# DistrValveBrd.net
KiCad netlist of a schematic drawn in Altium Designer
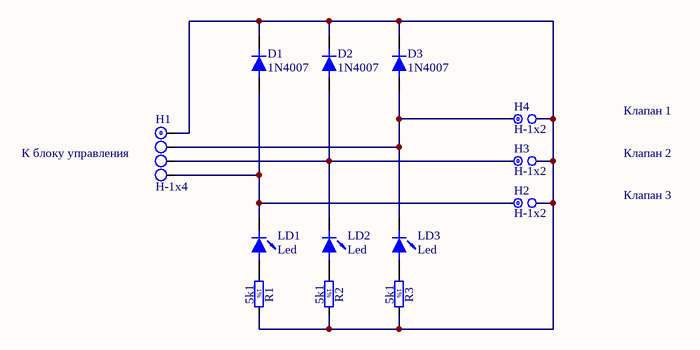
[diagram p0: DistrValveBrd.SchDoc]

(export (version "E")
  (design (tool "Eeschema 10.0.6"))
  (components
    (comp (ref "D1")
      (value "1N4007")
      (footprint "DO-41-300")
      (description "1000V 1A")
      (libsource (lib "Diodes-Power") (part "1N4007"))
    )
    (comp (ref "D2")
      (value "1N4007")
      (footprint "DO-41-300")
      (description "1000V 1A")
      (libsource (lib "Diodes-Power") (part "1N4007"))
    )
    (comp (ref "D3")
      (value "1N4007")
      (footprint "DO-41-300")
      (description "1000V 1A")
      (libsource (lib "Diodes-Power") (part "1N4007"))
    )
    (comp (ref "H1") (value "H-1x4") (footprint "J1x4") (libsource (lib "Connektor") (part "H-1x4")))
    (comp (ref "H2") (value "H-1x2") (footprint "J1x2") (libsource (lib "Connektor") (part "H-1x2")))
    (comp (ref "H3") (value "H-1x2") (footprint "J1x2") (libsource (lib "Connektor") (part "H-1x2")))
    (comp (ref "H4") (value "H-1x2") (footprint "J1x2") (libsource (lib "Connektor") (part "H-1x2")))
    (comp (ref "LD1")
      (value "Led")
      (footprint "Led d5mm")
      (description "5mm")
      (libsource (lib "Ind LED-LCD") (part "Led-5mm"))
    )
    (comp (ref "LD2")
      (value "Led")
      (footprint "Led d5mm")
      (description "5mm")
      (libsource (lib "Ind LED-LCD") (part "Led-5mm"))
    )
    (comp (ref "LD3")
      (value "Led")
      (footprint "Led d5mm")
      (description "5mm")
      (libsource (lib "Ind LED-LCD") (part "Led-5mm"))
    )
    (comp (ref "R1")
      (value "5k1")
      (footprint "RESC2012X60N")
      (description "Resistor - 1%")
      (fields
        (field (name "PART NUMBER") "R0805_5K1_1%_0.125W_100PPM")
        (field (name "POWER") "0.125W")
        (field (name "AUTHOR") "CERN DEM JLC")
      )
      (libsource (lib "Resistors") (part "Resistor - 1%"))
    )
    (comp (ref "R2")
      (value "5k1")
      (footprint "RESC2012X60N")
      (description "Resistor - 1%")
      (fields
        (field (name "PART NUMBER") "R0805_5K1_1%_0.125W_100PPM")
        (field (name "POWER") "0.125W")
        (field (name "AUTHOR") "CERN DEM JLC")
      )
      (libsource (lib "Resistors") (part "Resistor - 1%"))
    )
    (comp (ref "R3")
      (value "5k1")
      (footprint "RESC2012X60N")
      (description "Resistor - 1%")
      (fields
        (field (name "PART NUMBER") "R0805_5K1_1%_0.125W_100PPM")
        (field (name "POWER") "0.125W")
        (field (name "AUTHOR") "CERN DEM JLC")
      )
      (libsource (lib "Resistors") (part "Resistor - 1%"))
    )
  )
  (nets
    (net (code "1") (name "Net-(D1-A)") (class "Default")
      (node (ref "D1") (pin "1") (pinfunction "A_1") (pintype "passive"))
      (node (ref "H1") (pin "4") (pinfunction "4_4") (pintype "passive"))
      (node (ref "H2") (pin "1") (pinfunction "1_1") (pintype "passive"))
      (node (ref "LD1") (pin "2") (pinfunction "K_2") (pintype "passive"))
    )
    (net (code "2") (name "Net-(D1-K)") (class "Default")
      (node (ref "D1") (pin "2") (pinfunction "K_2") (pintype "passive"))
      (node (ref "D2") (pin "2") (pinfunction "K_2") (pintype "passive"))
      (node (ref "D3") (pin "2") (pinfunction "K_2") (pintype "passive"))
      (node (ref "H1") (pin "1") (pinfunction "1_1") (pintype "passive"))
      (node (ref "H2") (pin "2") (pinfunction "2_2") (pintype "passive"))
      (node (ref "H3") (pin "2") (pinfunction "2_2") (pintype "passive"))
      (node (ref "H4") (pin "2") (pinfunction "2_2") (pintype "passive"))
      (node (ref "R1") (pin "2") (pinfunction "2_2") (pintype "passive"))
      (node (ref "R2") (pin "2") (pinfunction "2_2") (pintype "passive"))
      (node (ref "R3") (pin "2") (pinfunction "2_2") (pintype "passive"))
    )
    (net (code "3") (name "Net-(D2-A)") (class "Default")
      (node (ref "D2") (pin "1") (pinfunction "A_1") (pintype "passive"))
      (node (ref "H1") (pin "3") (pinfunction "3_3") (pintype "passive"))
      (node (ref "H3") (pin "1") (pinfunction "1_1") (pintype "passive"))
      (node (ref "LD2") (pin "2") (pinfunction "K_2") (pintype "passive"))
    )
    (net (code "4") (name "Net-(D3-A)") (class "Default")
      (node (ref "D3") (pin "1") (pinfunction "A_1") (pintype "passive"))
      (node (ref "H1") (pin "2") (pinfunction "2_2") (pintype "passive"))
      (node (ref "H4") (pin "1") (pinfunction "1_1") (pintype "passive"))
      (node (ref "LD3") (pin "2") (pinfunction "K_2") (pintype "passive"))
    )
    (net (code "5") (name "Net-(LD1-A)") (class "Default")
      (node (ref "LD1") (pin "1") (pinfunction "A_1") (pintype "passive"))
      (node (ref "R1") (pin "1") (pinfunction "1_1") (pintype "passive"))
    )
    (net (code "6") (name "Net-(LD2-A)") (class "Default")
      (node (ref "LD2") (pin "1") (pinfunction "A_1") (pintype "passive"))
      (node (ref "R2") (pin "1") (pinfunction "1_1") (pintype "passive"))
    )
    (net (code "7") (name "Net-(LD3-A)") (class "Default")
      (node (ref "LD3") (pin "1") (pinfunction "A_1") (pintype "passive"))
      (node (ref "R3") (pin "1") (pinfunction "1_1") (pintype "passive"))
    )
  )
)
